# PSU.net
KiCad netlist of a schematic drawn in Altium Designer
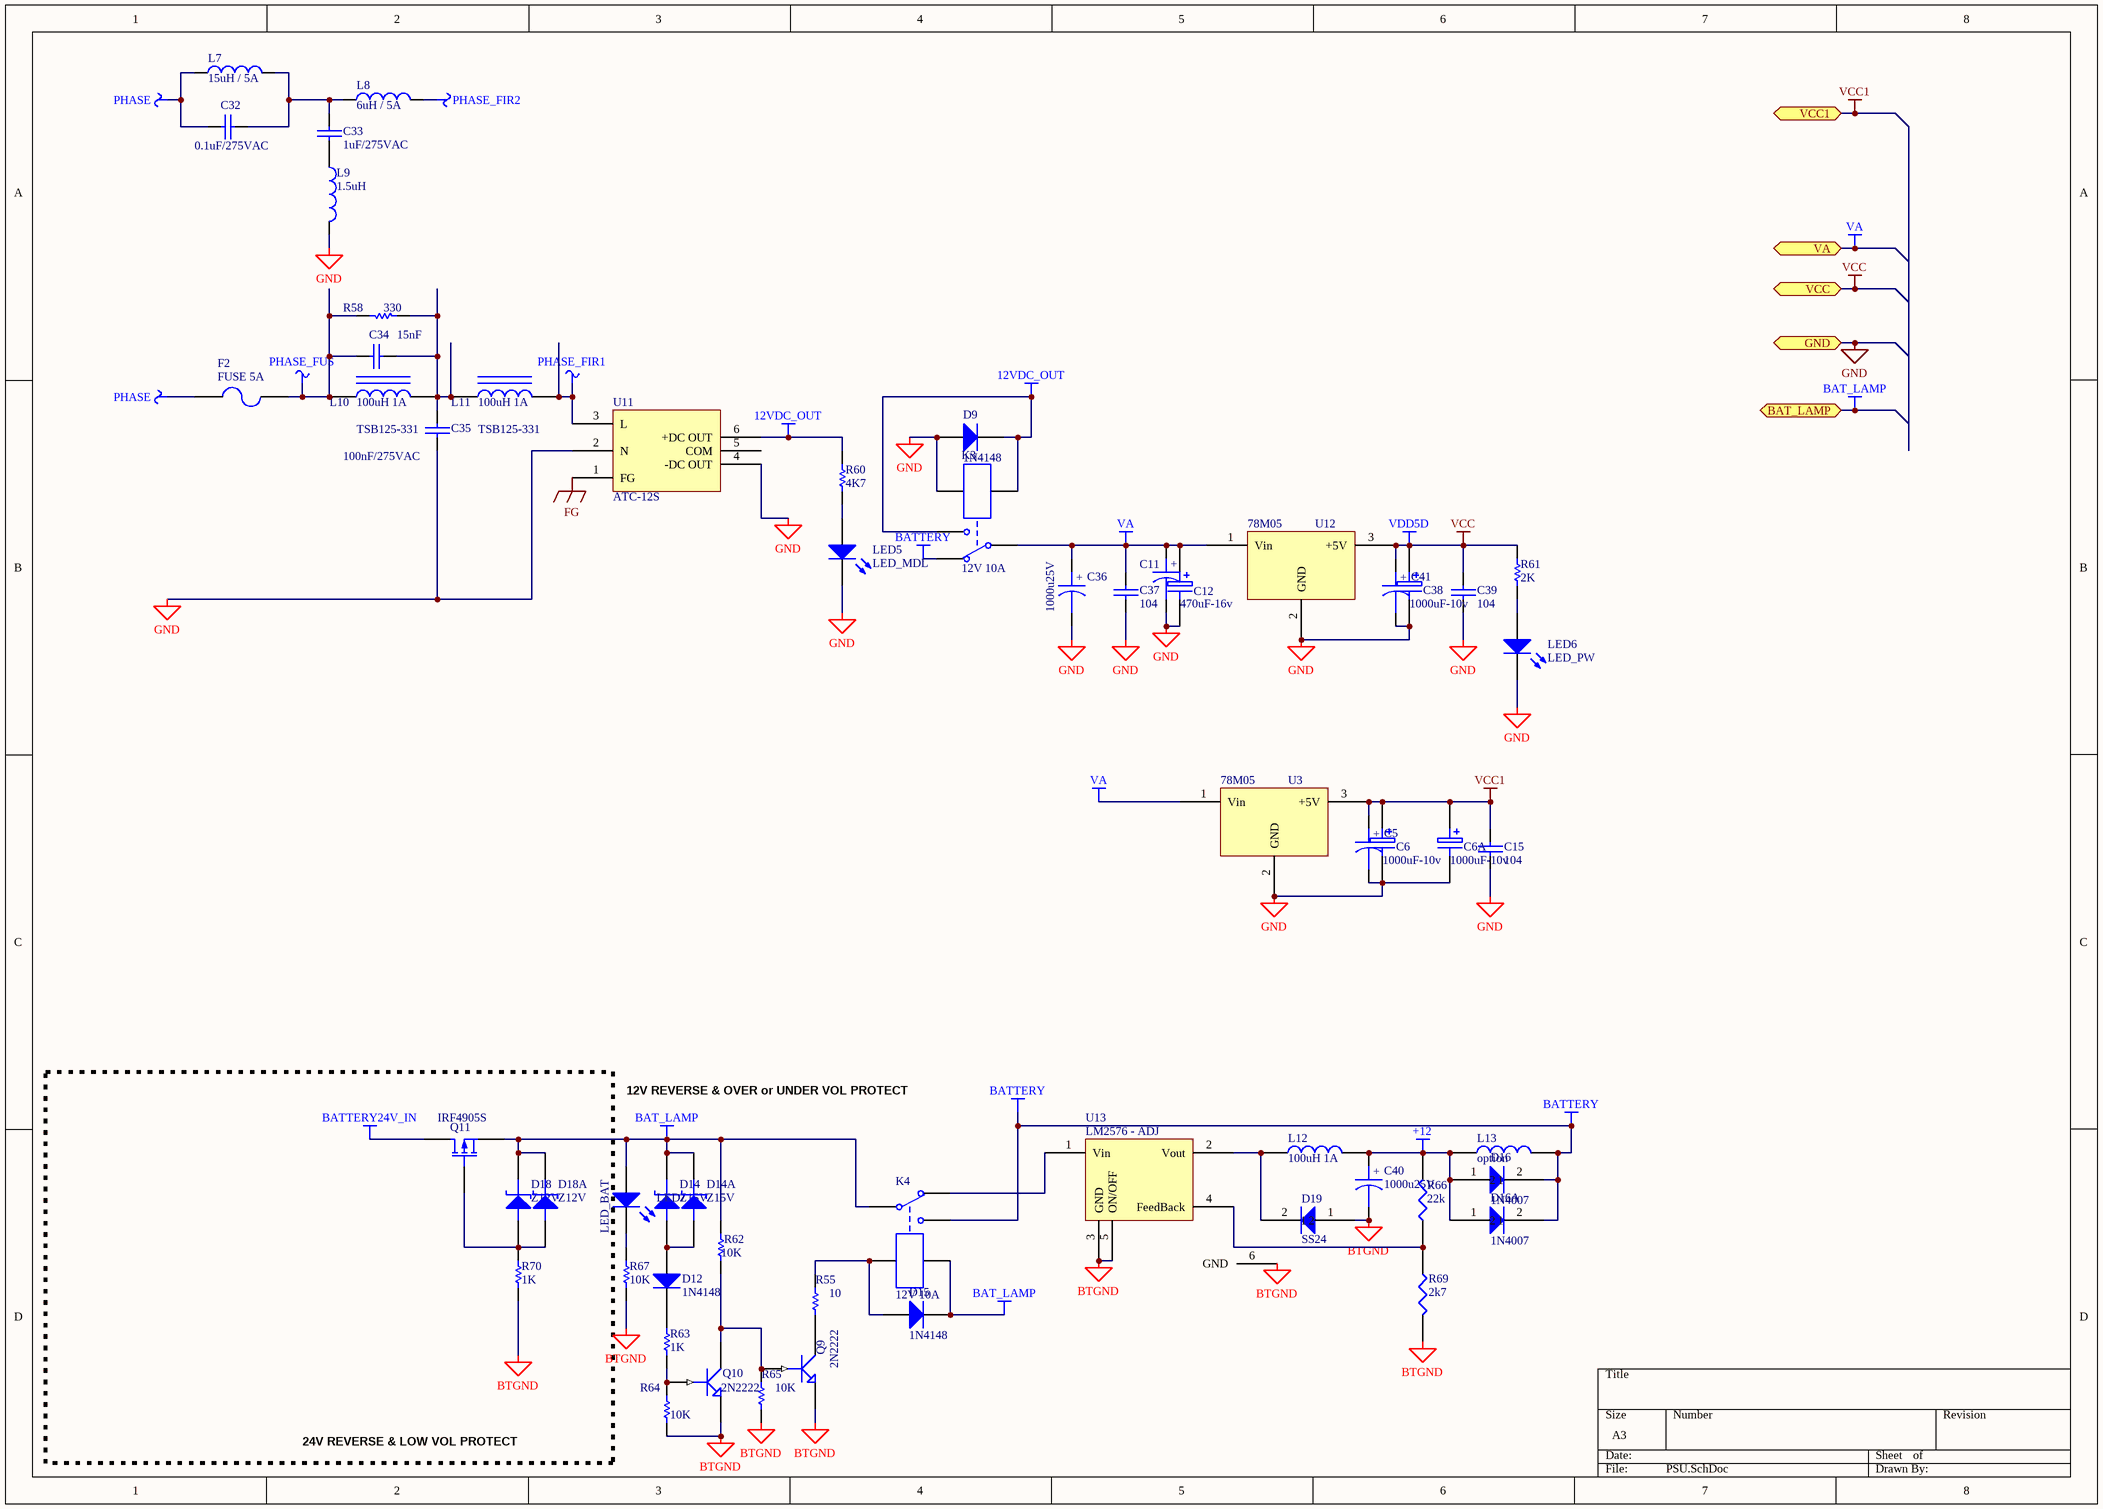
[diagram p0: PSU.SchDoc]

(export (version "E")
  (design (tool "Eeschema 10.0.6"))
  (components
    (comp (ref "C5")
      (value "1000u25V")
      (footprint "CAP40x20")
      (description "Capacitor")
      (libsource (lib "*") (part "CAPACITOR POL"))
    )
    (comp (ref "C6")
      (value "1000uF-10v")
      (footprint "CAP_ELEC_SIZE_E")
      (description "Electrolytic Capacitor")
      (libsource (lib "*") (part "ELECTRO1"))
    )
    (comp (ref "C6A")
      (value "1000uF-10v")
      (footprint "CAP_ELEC_SIZE_E")
      (description "Electrolytic Capacitor")
      (libsource (lib "*") (part "ELECTRO1"))
    )
    (comp (ref "C11")
      (value "1000u25V")
      (footprint "CAP40x20")
      (description "Capacitor")
      (libsource (lib "*") (part "CAPACITOR POL"))
    )
    (comp (ref "C12")
      (value "470uF-16v")
      (footprint "CAP_ELEC_SIZE_E")
      (description "Electrolytic Capacitor")
      (libsource (lib "*") (part "ELECTRO1"))
    )
    (comp (ref "C15")
      (value "104")
      (footprint "C6-0805_N")
      (description "Capacitor")
      (libsource (lib "*") (part "CAP"))
    )
    (comp (ref "C32")
      (value "0.1uF/275VAC")
      (footprint "100n400v")
      (description "0.1uF/275VAC X2")
      (libsource (lib "*") (part "CAP"))
    )
    (comp (ref "C33")
      (value "1uF/275VAC")
      (footprint "CAP1.2/0.5")
      (description "1uF/275VAC X2")
      (libsource (lib "*") (part "CAP"))
    )
    (comp (ref "C34")
      (value "15nF")
      (footprint "R3216[1206]")
      (description "Capacitor")
      (libsource (lib "*") (part "CAP"))
    )
    (comp (ref "C35")
      (value "100nF/275VAC")
      (footprint "100n400v")
      (description "100nF/275VAC X2")
      (libsource (lib "*") (part "CAP"))
    )
    (comp (ref "C36")
      (value "1000u25V")
      (footprint "CAP40x20")
      (description "Capacitor")
      (libsource (lib "*") (part "CAPACITOR POL"))
    )
    (comp (ref "C37")
      (value "104")
      (footprint "C6-0805_N")
      (description "Capacitor")
      (libsource (lib "*") (part "CAP"))
    )
    (comp (ref "C38")
      (value "1000uF-10v")
      (footprint "CAP_ELEC_SIZE_E")
      (description "Electrolytic Capacitor")
      (libsource (lib "*") (part "ELECTRO1"))
    )
    (comp (ref "C39")
      (value "104")
      (footprint "C6-0805_N")
      (description "Capacitor")
      (libsource (lib "*") (part "CAP"))
    )
    (comp (ref "C40")
      (value "1000u25V")
      (footprint "CAP40x20")
      (description "Capacitor")
      (libsource (lib "*") (part "CAPACITOR POL"))
    )
    (comp (ref "C41")
      (value "1000u25V")
      (footprint "CAP40x20")
      (description "Capacitor")
      (libsource (lib "*") (part "CAPACITOR POL"))
    )
    (comp (ref "D9")
      (value "1N4148")
      (footprint "SOD80, LL-34")
      (description "1 Amp General Purpose Rectifier")
      (fields (field (name "PUBLISHER") "Altium Limited"))
      (libsource (lib "*") (part "Diode 1N4007"))
    )
    (comp (ref "D12")
      (value "1N4148")
      (footprint "SOD80, LL-34")
      (description "1 Amp General Purpose Rectifier")
      (fields (field (name "PUBLISHER") "Altium Limited"))
      (libsource (lib "*") (part "Diode 1N4007"))
    )
    (comp (ref "D14")
      (value "Z15V")
      (footprint "DO-35")
      (description "Zener Diode")
      (libsource (lib "*") (part "ZENER2"))
    )
    (comp (ref "D14A")
      (value "Z15V")
      (footprint "SOT23-3")
      (description "Zener Diode")
      (libsource (lib "*") (part "ZENER2"))
    )
    (comp (ref "D15")
      (value "1N4148")
      (footprint "SOD80, LL-34")
      (description "1 Amp General Purpose Rectifier")
      (fields (field (name "PUBLISHER") "Altium Limited"))
      (libsource (lib "*") (part "Diode 1N4007"))
    )
    (comp (ref "D16")
      (value "1N4007")
      (footprint "DO-214AA")
      (description "Hoangphat")
      (libsource (lib "*") (part "DIODE"))
    )
    (comp (ref "D16A")
      (value "1N4007")
      (footprint "DO-214AA")
      (description "Hoangphat")
      (libsource (lib "*") (part "DIODE"))
    )
    (comp (ref "D18")
      (value "Z12V")
      (footprint "DO-35")
      (description "Zener Diode")
      (libsource (lib "*") (part "ZENER2"))
    )
    (comp (ref "D18A")
      (value "Z12V")
      (footprint "SOD80, LL-34")
      (description "Zener Diode")
      (libsource (lib "*") (part "ZENER2"))
    )
    (comp (ref "D19")
      (value "SS24")
      (footprint "DO-214AA")
      (description "Hoangphat")
      (libsource (lib "*") (part "DIODE"))
    )
    (comp (ref "F2")
      (value "FUSE 5A")
      (footprint "FUSE2")
      (description "Fuse")
      (libsource (lib "*") (part "FUSE2"))
    )
    (comp (ref "K3")
      (value "12V 10A")
      (footprint "RELAYVUONG")
      (description "G5LA-10A/250VAC / SRC-12VDC-SL-C")
      (fields (field (name "PUBLISHER") "Altium Limited"))
      (libsource (lib "Miscellaneous Devices") (part "Relay-SPDT"))
    )
    (comp (ref "K4")
      (value "12V 10A")
      (footprint "RELAYVUONG")
      (description "G5LA-10A/250VAC / SRC-12VDC-SL-C")
      (fields (field (name "PUBLISHER") "Altium Limited"))
      (libsource (lib "Miscellaneous Devices") (part "Relay-SPDT"))
    )
    (comp (ref "L7")
      (value "15uH / 5A")
      (footprint "IND26x8")
      (description "Toirodal Inductor")
      (fields (field (name "PUBLISHER") "Altium Limited"))
      (libsource (lib "Miscellaneous Devices") (part "Inductor"))
    )
    (comp (ref "L8")
      (value "6uH / 5A")
      (footprint "IND15X7")
      (description "Toirodal Inductor")
      (fields (field (name "PUBLISHER") "Altium Limited"))
      (libsource (lib "Miscellaneous Devices") (part "Inductor"))
    )
    (comp (ref "L9")
      (value "1.5uH")
      (footprint "IND15x7")
      (description "Toirodal Inductor")
      (fields (field (name "PUBLISHER") "Altium Limited"))
      (libsource (lib "Miscellaneous Devices") (part "Inductor"))
    )
    (comp (ref "L10")
      (value "100uH 1A")
      (footprint "IND1207")
      (description "100uH 1A SMD HP")
      (fields (field (name "ALTIUM_VALUE") "TSB125-331"))
      (libsource (lib "*") (part "INDUCTOR IRON"))
    )
    (comp (ref "L11")
      (value "100uH 1A")
      (footprint "IND1207")
      (description "100uH 1A SMD HP")
      (fields (field (name "ALTIUM_VALUE") "TSB125-331"))
      (libsource (lib "*") (part "INDUCTOR IRON"))
    )
    (comp (ref "L12") (value "100uH 1A") (footprint "IND1207") (libsource (lib "*") (part "INDUCTOR")))
    (comp (ref "L13") (value "option") (footprint "axial-0.3") (libsource (lib "*") (part "INDUCTOR")))
    (comp (ref "LED5")
      (value "LED_MDL")
      (footprint "LED3mm")
      (description "Typical BLUE SiC LED")
      (fields (field (name "PUBLISHER") "Altium Limited"))
      (libsource (lib "Miscellaneous Devices") (part "LED3"))
    )
    (comp (ref "LED6")
      (value "LED_PW")
      (footprint "LED3mm")
      (description "Typical BLUE SiC LED")
      (fields (field (name "PUBLISHER") "Altium Limited"))
      (libsource (lib "Miscellaneous Devices") (part "LED3"))
    )
    (comp (ref "LED7")
      (value "LED_BAT")
      (footprint "LED3mm")
      (description "Typical BLUE SiC LED")
      (fields (field (name "PUBLISHER") "Altium Limited"))
      (libsource (lib "Miscellaneous Devices") (part "LED3"))
    )
    (comp (ref "Q9")
      (value "2N2222")
      (footprint "SOT23-3")
      (description "NPN Transistor")
      (libsource (lib "*") (part "NPN1"))
    )
    (comp (ref "Q10")
      (value "2N2222")
      (footprint "SOT23-3")
      (description "NPN Transistor")
      (libsource (lib "*") (part "NPN1"))
    )
    (comp (ref "Q11")
      (value "IRF4905S")
      (footprint "D2PAK-3")
      (description "HEXFET Power P MOSFET")
      (fields (field (name "PUBLISHER") "Altium Limited"))
      (libsource (lib "Miscellaneous Devices") (part "MOSFET-P"))
    )
    (comp (ref "R55")
      (value "10")
      (footprint "6-0805_N")
      (description "Semiconductor Resistor")
      (fields (field (name "PUBLISHER") "*"))
      (libsource (lib "*") (part "Res Semi"))
    )
    (comp (ref "R58")
      (value "330")
      (footprint "R3216[1206]")
      (description "Semiconductor Resistor")
      (fields (field (name "PUBLISHER") "Altium Limited"))
      (libsource (lib "*") (part "Res Semi"))
    )
    (comp (ref "R60")
      (value "4K7")
      (footprint "6-0805_N")
      (description "Semiconductor Resistor")
      (fields (field (name "PUBLISHER") "*"))
      (libsource (lib "*") (part "Res Semi"))
    )
    (comp (ref "R61")
      (value "2K")
      (footprint "6-0805_N")
      (description "Semiconductor Resistor")
      (fields (field (name "PUBLISHER") "*"))
      (libsource (lib "*") (part "Res Semi"))
    )
    (comp (ref "R62")
      (value "10K")
      (footprint "6-0805_N")
      (description "Semiconductor Resistor")
      (fields (field (name "PUBLISHER") "*"))
      (libsource (lib "*") (part "Res Semi"))
    )
    (comp (ref "R63")
      (value "1K")
      (footprint "6-0805_N")
      (description "Semiconductor Resistor")
      (fields (field (name "PUBLISHER") "*"))
      (libsource (lib "*") (part "Res Semi"))
    )
    (comp (ref "R64")
      (value "10K")
      (footprint "6-0805_N")
      (description "Semiconductor Resistor")
      (fields (field (name "PUBLISHER") "*"))
      (libsource (lib "*") (part "Res Semi"))
    )
    (comp (ref "R65")
      (value "10K")
      (footprint "6-0805_N")
      (description "Semiconductor Resistor")
      (fields (field (name "PUBLISHER") "*"))
      (libsource (lib "*") (part "Res Semi"))
    )
    (comp (ref "R66") (value "22k") (footprint "6-0805_N") (libsource (lib "*") (part "RES1")))
    (comp (ref "R67")
      (value "10K")
      (footprint "6-0805_N")
      (description "Semiconductor Resistor")
      (fields (field (name "PUBLISHER") "*"))
      (libsource (lib "*") (part "Res Semi"))
    )
    (comp (ref "R69") (value "2k7") (footprint "6-0805_N") (libsource (lib "*") (part "RES1")))
    (comp (ref "R70")
      (value "1K")
      (footprint "6-0805_N")
      (description "Semiconductor Resistor")
      (fields (field (name "PUBLISHER") "*"))
      (libsource (lib "*") (part "Res Semi"))
    )
    (comp (ref "U3") (value "78M05") (footprint "D2PAK-3") (libsource (lib "*") (part "MC7805T")))
    (comp (ref "U11")
      (value "ATC-12S")
      (footprint "ATC MODULE")
      (libsource (lib "Schlib1") (part "Component_1"))
    )
    (comp (ref "U12") (value "78M05") (footprint "D2PAK-3") (libsource (lib "*") (part "MC7805T")))
    (comp (ref "U13") (value "LM2576 - ADJ") (footprint "TO-263-5") (libsource (lib "*") (part "LM2576")))
  )
  (nets
    (net (code "1") (name "+12") (class "Default")
      (node (ref "C40") (pin "1") (pinfunction "1_1") (pintype "passive"))
      (node (ref "D16") (pin "1") (pinfunction "1_1") (pintype "passive"))
      (node (ref "D16A") (pin "1") (pinfunction "1_1") (pintype "passive"))
      (node (ref "L12") (pin "2") (pinfunction "2_2") (pintype "passive"))
      (node (ref "L13") (pin "1") (pinfunction "1_1") (pintype "passive"))
      (node (ref "R66") (pin "2") (pinfunction "2_2") (pintype "passive"))
    )
    (net (code "2") (name "12VDC_OUT") (class "Default")
      (node (ref "D9") (pin "2") (pinfunction "K_2") (pintype "passive"))
      (node (ref "K3") (pin "3") (pinfunction "3_3") (pintype "passive"))
      (node (ref "K3") (pin "4") (pinfunction "4_4") (pintype "passive"))
      (node (ref "R60") (pin "2") (pinfunction "2_2") (pintype "passive"))
      (node (ref "U11") (pin "6") (pinfunction "+DC_OUT_6") (pintype "passive"))
    )
    (net (code "3") (name "BATTERY") (class "Default")
      (node (ref "D16") (pin "2") (pinfunction "2_2") (pintype "passive"))
      (node (ref "D16A") (pin "2") (pinfunction "2_2") (pintype "passive"))
      (node (ref "K3") (pin "2") (pinfunction "2_2") (pintype "passive"))
      (node (ref "K4") (pin "3") (pinfunction "3_3") (pintype "passive"))
      (node (ref "L13") (pin "2") (pinfunction "2_2") (pintype "passive"))
    )
    (net (code "4") (name "BATTERY24V_IN") (class "Default")
      (node (ref "Q11") (pin "2") (pinfunction "D_2") (pintype "passive"))
    )
    (net (code "5") (name "BAT_LAMP") (class "Default")
      (node (ref "D14") (pin "2") (pinfunction "K_2") (pintype "passive"))
      (node (ref "D14A") (pin "2") (pinfunction "K_2") (pintype "passive"))
      (node (ref "D15") (pin "2") (pinfunction "K_2") (pintype "passive"))
      (node (ref "D18") (pin "2") (pinfunction "K_2") (pintype "passive"))
      (node (ref "D18A") (pin "2") (pinfunction "K_2") (pintype "passive"))
      (node (ref "K4") (pin "1") (pinfunction "1_1") (pintype "passive"))
      (node (ref "K4") (pin "5") (pinfunction "5_5") (pintype "passive"))
      (node (ref "LED7") (pin "1") (pinfunction "A_1") (pintype "passive"))
      (node (ref "Q11") (pin "3") (pinfunction "S_3") (pintype "passive"))
      (node (ref "R62") (pin "2") (pinfunction "2_2") (pintype "passive"))
    )
    (net (code "6") (name "BTGND") (class "Default")
      (node (ref "C40") (pin "2") (pinfunction "2_2") (pintype "passive"))
      (node (ref "D19") (pin "1") (pinfunction "1_1") (pintype "passive"))
      (node (ref "Q10") (pin "2") (pinfunction "E_2") (pintype "passive"))
      (node (ref "Q9") (pin "2") (pinfunction "E_2") (pintype "passive"))
      (node (ref "R64") (pin "1") (pinfunction "1_1") (pintype "passive"))
      (node (ref "R65") (pin "1") (pinfunction "1_1") (pintype "passive"))
      (node (ref "R67") (pin "1") (pinfunction "1_1") (pintype "passive"))
      (node (ref "R69") (pin "2") (pinfunction "2_2") (pintype "passive"))
      (node (ref "R70") (pin "1") (pinfunction "1_1") (pintype "passive"))
      (node (ref "U13") (pin "3") (pinfunction "GND_3") (pintype "passive"))
      (node (ref "U13") (pin "5") (pinfunction "ON/OFF_5") (pintype "passive"))
      (node (ref "U13") (pin "6") (pinfunction "GND_6") (pintype "passive"))
    )
    (net (code "7") (name "FG") (class "Default")
      (node (ref "U11") (pin "1") (pinfunction "FG_1") (pintype "passive"))
    )
    (net (code "8") (name "GND") (class "Default")
      (node (ref "C11") (pin "2") (pinfunction "2_2") (pintype "passive"))
      (node (ref "C12") (pin "2") (pinfunction "2_2") (pintype "passive"))
      (node (ref "C15") (pin "2") (pinfunction "2_2") (pintype "passive"))
      (node (ref "C35") (pin "1") (pinfunction "1_1") (pintype "passive"))
      (node (ref "C36") (pin "2") (pinfunction "2_2") (pintype "passive"))
      (node (ref "C37") (pin "2") (pinfunction "2_2") (pintype "passive"))
      (node (ref "C38") (pin "2") (pinfunction "2_2") (pintype "passive"))
      (node (ref "C39") (pin "2") (pinfunction "2_2") (pintype "passive"))
      (node (ref "C41") (pin "2") (pinfunction "2_2") (pintype "passive"))
      (node (ref "C5") (pin "2") (pinfunction "2_2") (pintype "passive"))
      (node (ref "C6") (pin "2") (pinfunction "2_2") (pintype "passive"))
      (node (ref "C6A") (pin "2") (pinfunction "2_2") (pintype "passive"))
      (node (ref "D9") (pin "1") (pinfunction "A_1") (pintype "passive"))
      (node (ref "K3") (pin "5") (pinfunction "5_5") (pintype "passive"))
      (node (ref "L9") (pin "2") (pinfunction "2_2") (pintype "passive"))
      (node (ref "LED5") (pin "2") (pinfunction "K_2") (pintype "passive"))
      (node (ref "LED6") (pin "2") (pinfunction "K_2") (pintype "passive"))
      (node (ref "U11") (pin "2") (pinfunction "N_2") (pintype "passive"))
      (node (ref "U11") (pin "4") (pinfunction "-DC_OUT_4") (pintype "passive"))
      (node (ref "U12") (pin "2") (pinfunction "GND_2") (pintype "passive"))
      (node (ref "U3") (pin "2") (pinfunction "GND_2") (pintype "passive"))
    )
    (net (code "9") (name "Net-(C32-Pad1)") (class "Default")
      (node (ref "C32") (pin "1") (pinfunction "1_1") (pintype "passive"))
      (node (ref "C33") (pin "1") (pinfunction "1_1") (pintype "passive"))
      (node (ref "L7") (pin "2") (pinfunction "2_2") (pintype "passive"))
      (node (ref "L8") (pin "1") (pinfunction "1_1") (pintype "passive"))
    )
    (net (code "10") (name "Net-(C33-Pad2)") (class "Default")
      (node (ref "C33") (pin "2") (pinfunction "2_2") (pintype "passive"))
      (node (ref "L9") (pin "1") (pinfunction "1_1") (pintype "passive"))
    )
    (net (code "11") (name "Net-(C34-Pad2)") (class "Default")
      (node (ref "C34") (pin "2") (pinfunction "2_2") (pintype "passive"))
      (node (ref "C35") (pin "2") (pinfunction "2_2") (pintype "passive"))
      (node (ref "L10") (pin "2") (pinfunction "2_2") (pintype "passive"))
      (node (ref "L11") (pin "1") (pinfunction "1_1") (pintype "passive"))
      (node (ref "R58") (pin "1") (pinfunction "1_1") (pintype "passive"))
    )
    (net (code "12") (name "Net-(D12-A)") (class "Default")
      (node (ref "D12") (pin "1") (pinfunction "A_1") (pintype "passive"))
      (node (ref "D14") (pin "1") (pinfunction "A_1") (pintype "passive"))
      (node (ref "D14A") (pin "1") (pinfunction "A_1") (pintype "passive"))
    )
    (net (code "13") (name "Net-(D12-K)") (class "Default")
      (node (ref "D12") (pin "2") (pinfunction "K_2") (pintype "passive"))
      (node (ref "R63") (pin "2") (pinfunction "2_2") (pintype "passive"))
    )
    (net (code "14") (name "Net-(D15-A)") (class "Default")
      (node (ref "D15") (pin "1") (pinfunction "A_1") (pintype "passive"))
      (node (ref "K4") (pin "4") (pinfunction "4_4") (pintype "passive"))
      (node (ref "R55") (pin "2") (pinfunction "2_2") (pintype "passive"))
    )
    (net (code "15") (name "Net-(D18-A)") (class "Default")
      (node (ref "D18") (pin "1") (pinfunction "A_1") (pintype "passive"))
      (node (ref "D18A") (pin "1") (pinfunction "A_1") (pintype "passive"))
      (node (ref "Q11") (pin "1") (pinfunction "G_1") (pintype "passive"))
      (node (ref "R70") (pin "2") (pinfunction "2_2") (pintype "passive"))
    )
    (net (code "16") (name "Net-(LED5-A)") (class "Default")
      (node (ref "LED5") (pin "1") (pinfunction "A_1") (pintype "passive"))
      (node (ref "R60") (pin "1") (pinfunction "1_1") (pintype "passive"))
    )
    (net (code "17") (name "Net-(LED6-A)") (class "Default")
      (node (ref "LED6") (pin "1") (pinfunction "A_1") (pintype "passive"))
      (node (ref "R61") (pin "1") (pinfunction "1_1") (pintype "passive"))
    )
    (net (code "18") (name "Net-(LED7-K)") (class "Default")
      (node (ref "LED7") (pin "2") (pinfunction "K_2") (pintype "passive"))
      (node (ref "R67") (pin "2") (pinfunction "2_2") (pintype "passive"))
    )
    (net (code "19") (name "Net-(Q9-C)") (class "Default")
      (node (ref "Q9") (pin "3") (pinfunction "C_3") (pintype "passive"))
      (node (ref "R55") (pin "1") (pinfunction "1_1") (pintype "passive"))
    )
    (net (code "20") (name "Net-(Q10-B)") (class "Default")
      (node (ref "Q10") (pin "1") (pinfunction "B_1") (pintype "input"))
      (node (ref "R63") (pin "1") (pinfunction "1_1") (pintype "passive"))
      (node (ref "R64") (pin "2") (pinfunction "2_2") (pintype "passive"))
    )
    (net (code "21") (name "Net-(Q10-C)") (class "Default")
      (node (ref "Q10") (pin "3") (pinfunction "C_3") (pintype "passive"))
      (node (ref "Q9") (pin "1") (pinfunction "B_1") (pintype "input"))
      (node (ref "R62") (pin "1") (pinfunction "1_1") (pintype "passive"))
      (node (ref "R65") (pin "2") (pinfunction "2_2") (pintype "passive"))
    )
    (net (code "22") (name "Net-(U13-FeedBack)") (class "Default")
      (node (ref "R66") (pin "1") (pinfunction "1_1") (pintype "passive"))
      (node (ref "R69") (pin "1") (pinfunction "1_1") (pintype "passive"))
      (node (ref "U13") (pin "4") (pinfunction "FeedBack_4") (pintype "passive"))
    )
    (net (code "23") (name "Net-(U13-Vin)") (class "Default")
      (node (ref "K4") (pin "2") (pinfunction "2_2") (pintype "passive"))
      (node (ref "U13") (pin "1") (pinfunction "Vin_1") (pintype "passive"))
    )
    (net (code "24") (name "Net-(U13-Vout)") (class "Default")
      (node (ref "D19") (pin "2") (pinfunction "2_2") (pintype "passive"))
      (node (ref "L12") (pin "1") (pinfunction "1_1") (pintype "passive"))
      (node (ref "U13") (pin "2") (pinfunction "Vout_2") (pintype "passive"))
    )
    (net (code "25") (name "PHASE") (class "Default")
      (node (ref "C32") (pin "2") (pinfunction "2_2") (pintype "passive"))
      (node (ref "F2") (pin "1") (pinfunction "1_1") (pintype "passive"))
      (node (ref "L7") (pin "1") (pinfunction "1_1") (pintype "passive"))
    )
    (net (code "26") (name "PHASE_FIR1") (class "Default")
      (node (ref "L11") (pin "2") (pinfunction "2_2") (pintype "passive"))
      (node (ref "U11") (pin "3") (pinfunction "L_3") (pintype "passive"))
    )
    (net (code "27") (name "PHASE_FIR2") (class "Default")
      (node (ref "L8") (pin "2") (pinfunction "2_2") (pintype "passive"))
    )
    (net (code "28") (name "PHASE_FUS") (class "Default")
      (node (ref "C34") (pin "1") (pinfunction "1_1") (pintype "passive"))
      (node (ref "F2") (pin "2") (pinfunction "2_2") (pintype "passive"))
      (node (ref "L10") (pin "1") (pinfunction "1_1") (pintype "passive"))
      (node (ref "R58") (pin "2") (pinfunction "2_2") (pintype "passive"))
    )
    (net (code "29") (name "VA") (class "Default")
      (node (ref "C11") (pin "1") (pinfunction "1_1") (pintype "passive"))
      (node (ref "C12") (pin "1") (pinfunction "1_1") (pintype "passive"))
      (node (ref "C36") (pin "1") (pinfunction "1_1") (pintype "passive"))
      (node (ref "C37") (pin "1") (pinfunction "1_1") (pintype "passive"))
      (node (ref "K3") (pin "1") (pinfunction "1_1") (pintype "passive"))
      (node (ref "U12") (pin "1") (pinfunction "Vin_1") (pintype "passive"))
      (node (ref "U3") (pin "1") (pinfunction "Vin_1") (pintype "passive"))
    )
    (net (code "30") (name "VCC") (class "Default")
      (node (ref "C38") (pin "1") (pinfunction "1_1") (pintype "passive"))
      (node (ref "C39") (pin "1") (pinfunction "1_1") (pintype "passive"))
      (node (ref "C41") (pin "1") (pinfunction "1_1") (pintype "passive"))
      (node (ref "R61") (pin "2") (pinfunction "2_2") (pintype "passive"))
      (node (ref "U12") (pin "3") (pinfunction "+5V_3") (pintype "passive"))
    )
    (net (code "31") (name "VCC1") (class "Default")
      (node (ref "C15") (pin "1") (pinfunction "1_1") (pintype "passive"))
      (node (ref "C5") (pin "1") (pinfunction "1_1") (pintype "passive"))
      (node (ref "C6") (pin "1") (pinfunction "1_1") (pintype "passive"))
      (node (ref "C6A") (pin "1") (pinfunction "1_1") (pintype "passive"))
      (node (ref "U3") (pin "3") (pinfunction "+5V_3") (pintype "passive"))
    )
    (net (code "32") (name "unconnected-(U11-COM-Pad5)") (class "Default")
      (node (ref "U11") (pin "5") (pinfunction "COM_5") (pintype "passive"))
    )
  )
)
